# Sheet1.net
KiCad netlist of a schematic drawn in Altium Designer
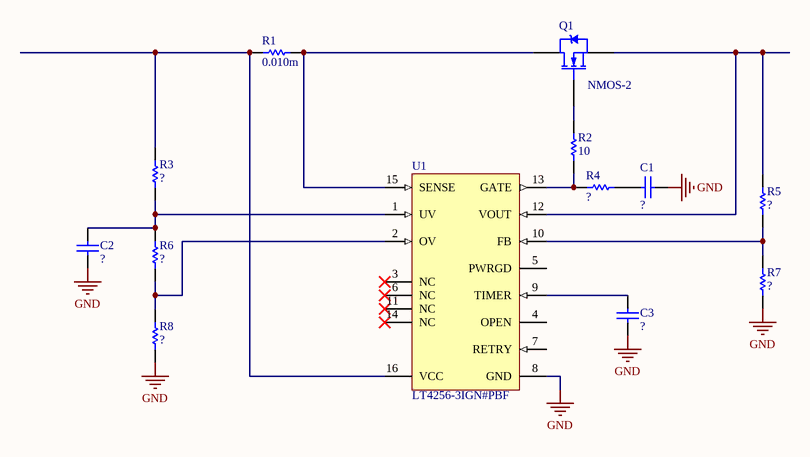
[diagram p0: Sheet1.SchDoc]

(export (version "E")
  (design (tool "Eeschema 10.0.6"))
  (components
    (comp (ref "C1")
      (value "?")
      (footprint "RAD-0.3")
      (description "Capacitor")
      (fields (field (name "Comment") "Cap") (field (name "PUBLISHER") "Altium Limited"))
      (libsource (lib "Miscellaneous Devices") (part "Cap"))
    )
    (comp (ref "C2")
      (value "?")
      (footprint "RAD-0.3")
      (description "Capacitor")
      (fields (field (name "Comment") "Cap") (field (name "PUBLISHER") "Altium Limited"))
      (libsource (lib "Miscellaneous Devices") (part "Cap"))
    )
    (comp (ref "C3")
      (value "?")
      (footprint "RAD-0.3")
      (description "Capacitor")
      (fields (field (name "Comment") "Cap") (field (name "PUBLISHER") "Altium Limited"))
      (libsource (lib "Miscellaneous Devices") (part "Cap"))
    )
    (comp (ref "Q1")
      (value "NMOS-2")
      (footprint "TO-220AB")
      (description "N-Channel Power MOSFET")
      (fields (field (name "PUBLISHER") "Altium Limited"))
      (libsource (lib "Miscellaneous Devices") (part "NMOS-2"))
    )
    (comp (ref "R1")
      (value "0.010m")
      (footprint "AXIAL-0.3")
      (description "Resistor")
      (fields (field (name "Comment") "Res1") (field (name "PUBLISHER") "Altium Limited"))
      (libsource (lib "Miscellaneous Devices") (part "Res1"))
    )
    (comp (ref "R2")
      (value "10")
      (footprint "AXIAL-0.3")
      (description "Resistor")
      (fields (field (name "Comment") "Res1") (field (name "PUBLISHER") "Altium Limited"))
      (libsource (lib "Miscellaneous Devices") (part "Res1"))
    )
    (comp (ref "R3")
      (value "?")
      (footprint "AXIAL-0.3")
      (description "Resistor")
      (fields (field (name "Comment") "Res1") (field (name "PUBLISHER") "Altium Limited"))
      (libsource (lib "Miscellaneous Devices") (part "Res1"))
    )
    (comp (ref "R4")
      (value "?")
      (footprint "AXIAL-0.3")
      (description "Resistor")
      (fields (field (name "Comment") "Res1") (field (name "PUBLISHER") "Altium Limited"))
      (libsource (lib "Miscellaneous Devices") (part "Res1"))
    )
    (comp (ref "R5")
      (value "?")
      (footprint "AXIAL-0.3")
      (description "Resistor")
      (fields (field (name "Comment") "Res1") (field (name "PUBLISHER") "Altium Limited"))
      (libsource (lib "Miscellaneous Devices") (part "Res1"))
    )
    (comp (ref "R6")
      (value "?")
      (footprint "AXIAL-0.3")
      (description "Resistor")
      (fields (field (name "Comment") "Res1") (field (name "PUBLISHER") "Altium Limited"))
      (libsource (lib "Miscellaneous Devices") (part "Res1"))
    )
    (comp (ref "R7")
      (value "?")
      (footprint "AXIAL-0.3")
      (description "Resistor")
      (fields (field (name "Comment") "Res1") (field (name "PUBLISHER") "Altium Limited"))
      (libsource (lib "Miscellaneous Devices") (part "Res1"))
    )
    (comp (ref "R8")
      (value "?")
      (footprint "AXIAL-0.3")
      (description "Resistor")
      (fields (field (name "Comment") "Res1") (field (name "PUBLISHER") "Altium Limited"))
      (libsource (lib "Miscellaneous Devices") (part "Res1"))
    )
    (comp (ref "U1")
      (value "LT4256-3IGN#PBF")
      (footprint "LT-GN-16_L")
      (fields (field (name "MANUFACTURER") "Linear Technology"))
      (libsource (lib "Altium Content Vault") (part "LT-LT4256-3-GN-16"))
    )
  )
  (nets
    (net (code "1") (name "GND") (class "Default")
      (node (ref "C1") (pin "1") (pinfunction "1_1") (pintype "passive"))
      (node (ref "C2") (pin "1") (pinfunction "1_1") (pintype "passive"))
      (node (ref "C3") (pin "1") (pinfunction "1_1") (pintype "passive"))
      (node (ref "R7") (pin "1") (pinfunction "1_1") (pintype "passive"))
      (node (ref "R8") (pin "1") (pinfunction "1_1") (pintype "passive"))
      (node (ref "U1") (pin "8") (pinfunction "GND_8") (pintype "power_in"))
    )
    (net (code "2") (name "Net-(C1-Pad2)") (class "Default")
      (node (ref "C1") (pin "2") (pinfunction "2_2") (pintype "passive"))
      (node (ref "R4") (pin "1") (pinfunction "1_1") (pintype "passive"))
    )
    (net (code "3") (name "Net-(Q1-D)") (class "Default")
      (node (ref "Q1") (pin "2") (pinfunction "D_2") (pintype "passive"))
      (node (ref "R1") (pin "2") (pinfunction "2_2") (pintype "passive"))
      (node (ref "U1") (pin "15") (pinfunction "SENSE_15") (pintype "input"))
    )
    (net (code "4") (name "Net-(Q1-G)") (class "Default")
      (node (ref "Q1") (pin "1") (pinfunction "G_1") (pintype "passive"))
      (node (ref "R2") (pin "2") (pinfunction "2_2") (pintype "passive"))
    )
    (net (code "5") (name "Net-(Q1-S)") (class "Default")
      (node (ref "Q1") (pin "3") (pinfunction "S_3") (pintype "passive"))
      (node (ref "R5") (pin "2") (pinfunction "2_2") (pintype "passive"))
      (node (ref "U1") (pin "12") (pinfunction "VOUT_12") (pintype "input"))
    )
    (net (code "6") (name "Net-(U1-FB)") (class "Default")
      (node (ref "R5") (pin "1") (pinfunction "1_1") (pintype "passive"))
      (node (ref "R7") (pin "2") (pinfunction "2_2") (pintype "passive"))
      (node (ref "U1") (pin "10") (pinfunction "FB_10") (pintype "input"))
    )
    (net (code "7") (name "Net-(U1-GATE)") (class "Default")
      (node (ref "R2") (pin "1") (pinfunction "1_1") (pintype "passive"))
      (node (ref "R4") (pin "2") (pinfunction "2_2") (pintype "passive"))
      (node (ref "U1") (pin "13") (pinfunction "GATE_13") (pintype "output"))
    )
    (net (code "8") (name "Net-(U1-OV)") (class "Default")
      (node (ref "R6") (pin "1") (pinfunction "1_1") (pintype "passive"))
      (node (ref "R8") (pin "2") (pinfunction "2_2") (pintype "passive"))
      (node (ref "U1") (pin "2") (pinfunction "OV_2") (pintype "input"))
    )
    (net (code "9") (name "Net-(U1-TIMER)") (class "Default")
      (node (ref "C3") (pin "2") (pinfunction "2_2") (pintype "passive"))
      (node (ref "U1") (pin "9") (pinfunction "TIMER_9") (pintype "input"))
    )
    (net (code "10") (name "Net-(U1-UV)") (class "Default")
      (node (ref "C2") (pin "2") (pinfunction "2_2") (pintype "passive"))
      (node (ref "R3") (pin "1") (pinfunction "1_1") (pintype "passive"))
      (node (ref "R6") (pin "2") (pinfunction "2_2") (pintype "passive"))
      (node (ref "U1") (pin "1") (pinfunction "UV_1") (pintype "input"))
    )
    (net (code "11") (name "Net-(U1-VCC)") (class "Default")
      (node (ref "R1") (pin "1") (pinfunction "1_1") (pintype "passive"))
      (node (ref "R3") (pin "2") (pinfunction "2_2") (pintype "passive"))
      (node (ref "U1") (pin "16") (pinfunction "VCC_16") (pintype "power_in"))
    )
    (net (code "12") (name "unconnected-(U1-NC-Pad3)") (class "Default")
      (node (ref "U1") (pin "3") (pinfunction "NC_3") (pintype "passive+no_connect"))
    )
    (net (code "13") (name "unconnected-(U1-NC-Pad6)") (class "Default")
      (node (ref "U1") (pin "6") (pinfunction "NC_6") (pintype "passive+no_connect"))
    )
    (net (code "14") (name "unconnected-(U1-NC-Pad11)") (class "Default")
      (node (ref "U1") (pin "11") (pinfunction "NC_11") (pintype "passive+no_connect"))
    )
    (net (code "15") (name "unconnected-(U1-NC-Pad14)") (class "Default")
      (node (ref "U1") (pin "14") (pinfunction "NC_14") (pintype "passive+no_connect"))
    )
    (net (code "16") (name "unconnected-(U1-OPEN-Pad4)") (class "Default")
      (node (ref "U1") (pin "4") (pinfunction "OPEN_4") (pintype "open_collector"))
    )
    (net (code "17") (name "unconnected-(U1-PWRGD-Pad5)") (class "Default")
      (node (ref "U1") (pin "5") (pinfunction "PWRGD_5") (pintype "tri_state"))
    )
    (net (code "18") (name "unconnected-(U1-RETRY-Pad7)") (class "Default")
      (node (ref "U1") (pin "7") (pinfunction "RETRY_7") (pintype "input"))
    )
  )
)
